# eye_junction.net
KiCad netlist of a schematic drawn in EAGLE
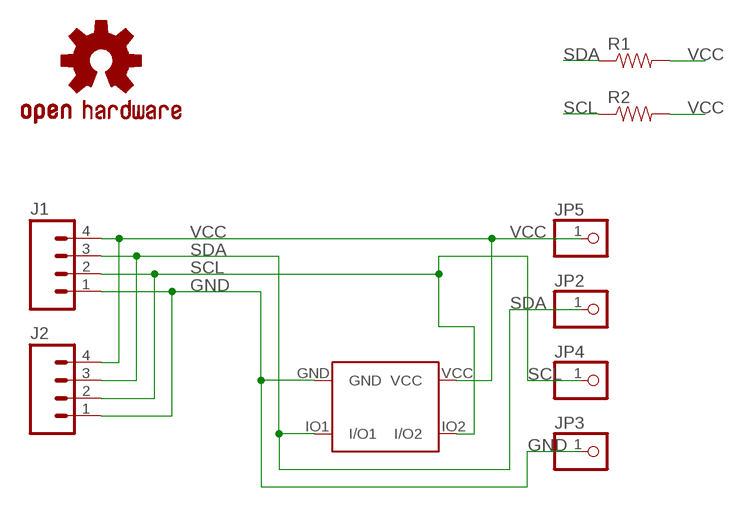
[diagram p0: schematic, sheet 1]

(export (version "E")
  (design (tool "Eeschema 10.0.6"))
  (components
    (comp (ref "J1")
      (value "M04JST-PTH-VERT")
      (footprint "eagle-import:JST-4-PTH-VERT")
      (libsource (lib "eagle-import") (part "M04JST-PTH-VERT"))
    )
    (comp (ref "J2")
      (value "M04JST-PTH-VERT")
      (footprint "eagle-import:JST-4-PTH-VERT")
      (libsource (lib "eagle-import") (part "M04JST-PTH-VERT"))
    )
    (comp (ref "JP2")
      (value "PINHD-1X1CB")
      (footprint "eagle-import:1X01-CLEANBIG")
      (libsource (lib "eagle-import") (part "PINHD-1X1CB"))
    )
    (comp (ref "JP3")
      (value "PINHD-1X1CB")
      (footprint "eagle-import:1X01-CLEANBIG")
      (libsource (lib "eagle-import") (part "PINHD-1X1CB"))
    )
    (comp (ref "JP4")
      (value "PINHD-1X1CB")
      (footprint "eagle-import:1X01-CLEANBIG")
      (libsource (lib "eagle-import") (part "PINHD-1X1CB"))
    )
    (comp (ref "JP5")
      (value "PINHD-1X1CB")
      (footprint "eagle-import:1X01-CLEANBIG")
      (libsource (lib "eagle-import") (part "PINHD-1X1CB"))
    )
    (comp (ref "LOGO1")
      (value "OSHW-LOGOS")
      (footprint "eagle-import:OSHW-LOGO-S")
      (libsource (lib "eagle-import") (part "OSHW-LOGOS"))
    )
    (comp (ref "R1")
      (value "RESISTORAXIAL-0.3")
      (footprint "eagle-import:AXIAL-0.3")
      (libsource (lib "eagle-import") (part "RESISTORAXIAL-0.3"))
    )
    (comp (ref "R2")
      (value "RESISTORAXIAL-0.3")
      (footprint "eagle-import:AXIAL-0.3")
      (libsource (lib "eagle-import") (part "RESISTORAXIAL-0.3"))
    )
    (comp (ref "U$2")
      (value "TVS_ARRAY_CD143A")
      (footprint "eagle-import:SOT-143")
      (libsource (lib "eagle-import") (part "TVS_ARRAY_CD143A"))
    )
  )
  (nets
    (net (code "1") (name "/GND") (class "Default")
      (node (ref "J1") (pin "1") (pinfunction "1_1") (pintype "passive"))
      (node (ref "J2") (pin "1") (pinfunction "1_1") (pintype "passive"))
      (node (ref "JP3") (pin "1") (pinfunction "1_1") (pintype "passive"))
      (node (ref "U$2") (pin "GND") (pinfunction "GND_GND") (pintype "power_in"))
    )
    (net (code "2") (name "/SCL") (class "Default")
      (node (ref "J1") (pin "2") (pinfunction "2_2") (pintype "passive"))
      (node (ref "J2") (pin "2") (pinfunction "2_2") (pintype "passive"))
      (node (ref "JP4") (pin "1") (pinfunction "1_1") (pintype "passive"))
      (node (ref "R2") (pin "P$1") (pinfunction "1_P$1") (pintype "passive"))
      (node (ref "U$2") (pin "IO2") (pinfunction "I/O2_IO2") (pintype "bidirectional"))
    )
    (net (code "3") (name "/SDA") (class "Default")
      (node (ref "J1") (pin "3") (pinfunction "3_3") (pintype "passive"))
      (node (ref "J2") (pin "3") (pinfunction "3_3") (pintype "passive"))
      (node (ref "JP2") (pin "1") (pinfunction "1_1") (pintype "passive"))
      (node (ref "R1") (pin "P$1") (pinfunction "1_P$1") (pintype "passive"))
      (node (ref "U$2") (pin "IO1") (pinfunction "I/O1_IO1") (pintype "bidirectional"))
    )
    (net (code "4") (name "/VCC") (class "Default")
      (node (ref "J1") (pin "4") (pinfunction "4_4") (pintype "passive"))
      (node (ref "J2") (pin "4") (pinfunction "4_4") (pintype "passive"))
      (node (ref "JP5") (pin "1") (pinfunction "1_1") (pintype "passive"))
      (node (ref "R1") (pin "P$2") (pinfunction "2_P$2") (pintype "passive"))
      (node (ref "R2") (pin "P$2") (pinfunction "2_P$2") (pintype "passive"))
      (node (ref "U$2") (pin "VCC") (pinfunction "VCC_VCC") (pintype "power_in"))
    )
  )
)
